# ESP12_Altherma.net
KiCad netlist of a schematic drawn in EAGLE
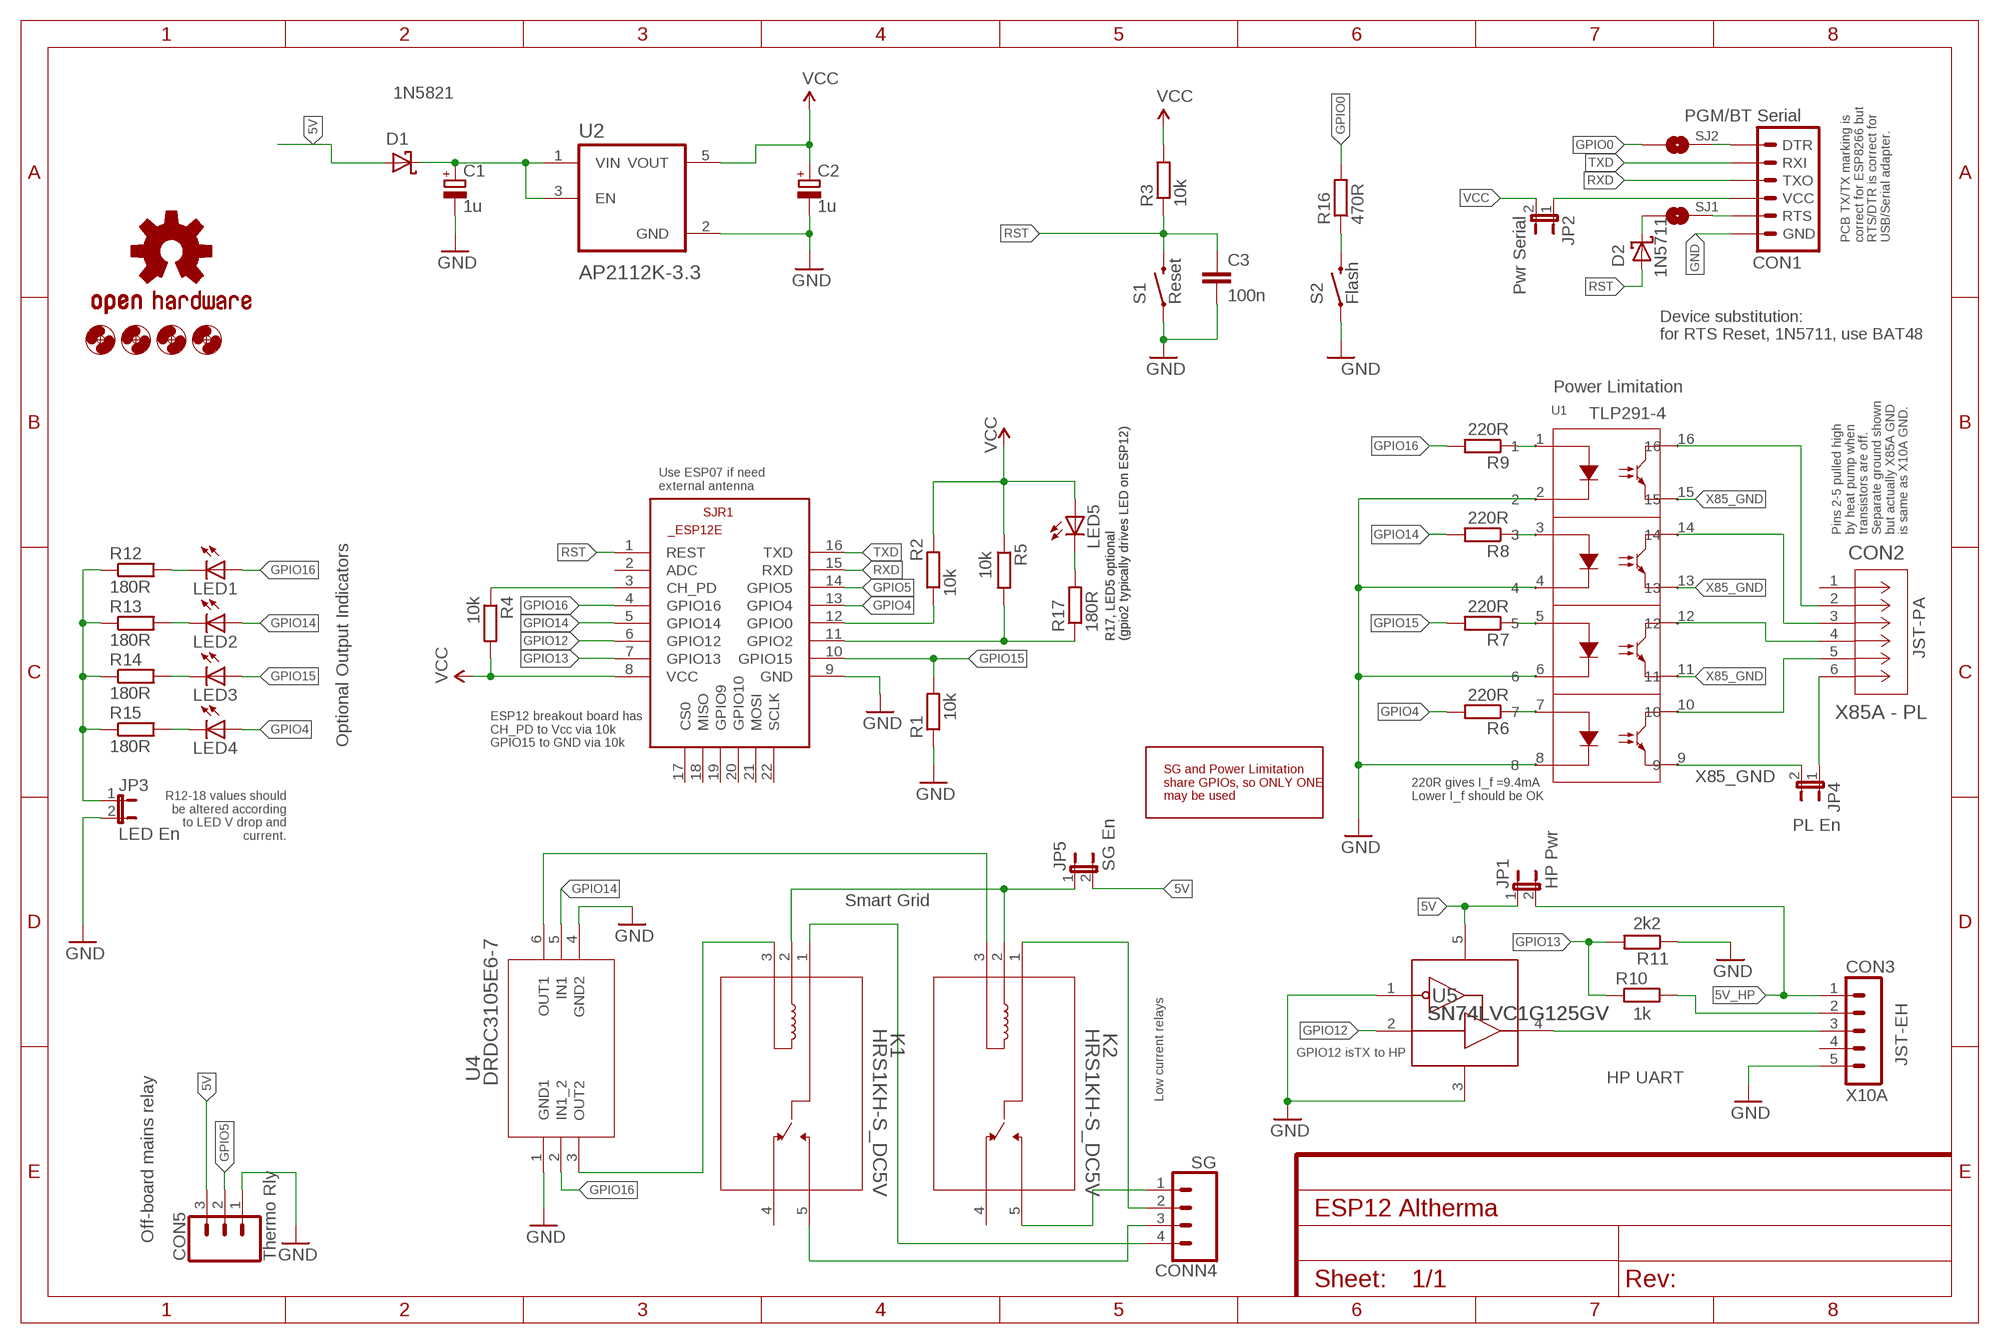
[diagram p0: schematic, sheet 1]

(export (version "E")
  (design (tool "Eeschema 10.0.6"))
  (components
    (comp (ref "C1")
      (value "1u")
      (footprint "eagle-import:E2,5-5")
      (libsource (lib "eagle-import") (part "CPOL-EUE2.5-510UF"))
    )
    (comp (ref "C2")
      (value "1u")
      (footprint "eagle-import:E2,5-5")
      (libsource (lib "eagle-import") (part "CPOL-EUE2.5-510UF"))
    )
    (comp (ref "C3")
      (value "100n")
      (footprint "eagle-import:1206")
      (libsource (lib "eagle-import") (part "C-EU1206"))
    )
    (comp (ref "CON1")
      (value "PGM/BT Serial")
      (footprint "eagle-import:1X06-KIT")
      (libsource (lib "eagle-import") (part "ESP8266_SERIAL_PROGRAM1X06_ESP_SERIAL"))
    )
    (comp (ref "CON2")
      (value "X85A - PL")
      (footprint "eagle-import:CONN_B06B-PASK_JST")
      (fields
        (field (name "MANUFACTURER_PART_NUMBER") "B06B-PASK(LF)(SN)")
        (field (name "COPYRIGHT") "Copyright (C) 2025 Ultra Librarian. All rights reserved.")
      )
      (libsource (lib "eagle-import") (part "B06B-PASK(LF)(SN)"))
    )
    (comp (ref "CON3")
      (value "X10A")
      (footprint "eagle-import:B5B-EH-A")
      (libsource (lib "eagle-import") (part "B5B-EH-A"))
    )
    (comp (ref "CON5")
      (value "Thermo Rly")
      (footprint "eagle-import:1X03")
      (libsource (lib "eagle-import") (part "CONN_03"))
    )
    (comp (ref "CONN4")
      (value "SG")
      (footprint "eagle-import:1X04")
      (libsource (lib "eagle-import") (part "CONN_04PTH"))
    )
    (comp (ref "D1")
      (value "1N5821")
      (footprint "eagle-import:DO201-15")
      (libsource (lib "eagle-import") (part "DIODE-SCHOTTKYDO-201-VERT"))
    )
    (comp (ref "D2")
      (value "1N5711")
      (footprint "eagle-import:DO35-7")
      (libsource (lib "eagle-import") (part "DIODE-SCHOTTKYDO35-7"))
    )
    (comp (ref "H1")
      (value "MOUNT-HOLE3.2")
      (footprint "eagle-import:3,2")
      (libsource (lib "eagle-import") (part "MOUNT-HOLE3.2"))
    )
    (comp (ref "H2")
      (value "MOUNT-HOLE3.2")
      (footprint "eagle-import:3,2")
      (libsource (lib "eagle-import") (part "MOUNT-HOLE3.2"))
    )
    (comp (ref "H3")
      (value "MOUNT-HOLE3.2")
      (footprint "eagle-import:3,2")
      (libsource (lib "eagle-import") (part "MOUNT-HOLE3.2"))
    )
    (comp (ref "H4")
      (value "MOUNT-HOLE3.2")
      (footprint "eagle-import:3,2")
      (libsource (lib "eagle-import") (part "MOUNT-HOLE3.2"))
    )
    (comp (ref "JP1")
      (value "HP Pwr")
      (footprint "eagle-import:1X02")
      (libsource (lib "eagle-import") (part "JUMPER-2PTH"))
    )
    (comp (ref "JP2")
      (value "Pwr Serial")
      (footprint "eagle-import:1X02")
      (libsource (lib "eagle-import") (part "JUMPER-2PTH"))
    )
    (comp (ref "JP3")
      (value "LED En")
      (footprint "eagle-import:1X02")
      (libsource (lib "eagle-import") (part "JUMPER-2PTH"))
    )
    (comp (ref "JP4")
      (value "PL En")
      (footprint "eagle-import:1X02")
      (libsource (lib "eagle-import") (part "JUMPER-2PTH"))
    )
    (comp (ref "JP5")
      (value "SG En")
      (footprint "eagle-import:1X02")
      (libsource (lib "eagle-import") (part "JUMPER-2PTH"))
    )
    (comp (ref "K1")
      (value "HRS1KH-S_DC5V")
      (footprint "eagle-import:HRS1KH-S_DC5V_MTC")
      (fields
        (field (name "MANUFACTURER_PART_NUMBER") "HRS1KH-S DC5V")
        (field (name "COPYRIGHT") "Copyright (C) 2024 Ultra Librarian. All rights reserved.")
      )
      (libsource (lib "eagle-import") (part "HRS1KH-S_DC5V"))
    )
    (comp (ref "K2")
      (value "HRS1KH-S_DC5V")
      (footprint "eagle-import:HRS1KH-S_DC5V_MTC")
      (fields
        (field (name "MANUFACTURER_PART_NUMBER") "HRS1KH-S DC5V")
        (field (name "COPYRIGHT") "Copyright (C) 2024 Ultra Librarian. All rights reserved.")
      )
      (libsource (lib "eagle-import") (part "HRS1KH-S_DC5V"))
    )
    (comp (ref "LED1")
      (value "LED1206")
      (footprint "eagle-import:LED-1206")
      (libsource (lib "eagle-import") (part "LED1206"))
    )
    (comp (ref "LED2")
      (value "LED1206")
      (footprint "eagle-import:LED-1206")
      (libsource (lib "eagle-import") (part "LED1206"))
    )
    (comp (ref "LED3")
      (value "LED1206")
      (footprint "eagle-import:LED-1206")
      (libsource (lib "eagle-import") (part "LED1206"))
    )
    (comp (ref "LED4")
      (value "LED1206")
      (footprint "eagle-import:LED-1206")
      (libsource (lib "eagle-import") (part "LED1206"))
    )
    (comp (ref "LED5")
      (value "LED1206")
      (footprint "eagle-import:LED-1206")
      (libsource (lib "eagle-import") (part "LED1206"))
    )
    (comp (ref "LOGO1")
      (value "OSHW-LOGOM")
      (footprint "eagle-import:OSHW-LOGO-M")
      (libsource (lib "eagle-import") (part "OSHW-LOGOM"))
    )
    (comp (ref "R1")
      (value "10k")
      (footprint "eagle-import:1206")
      (libsource (lib "eagle-import") (part "R-EU_"))
    )
    (comp (ref "R2")
      (value "10k")
      (footprint "eagle-import:1206")
      (libsource (lib "eagle-import") (part "R-EU_"))
    )
    (comp (ref "R3")
      (value "10k")
      (footprint "eagle-import:1206")
      (libsource (lib "eagle-import") (part "R-EU_"))
    )
    (comp (ref "R4")
      (value "10k")
      (footprint "eagle-import:1206")
      (libsource (lib "eagle-import") (part "R-EU_"))
    )
    (comp (ref "R5")
      (value "10k")
      (footprint "eagle-import:1206")
      (libsource (lib "eagle-import") (part "R-EU_"))
    )
    (comp (ref "R6")
      (value "220R")
      (footprint "eagle-import:1206")
      (libsource (lib "eagle-import") (part "R-EU_"))
    )
    (comp (ref "R7")
      (value "220R")
      (footprint "eagle-import:1206")
      (libsource (lib "eagle-import") (part "R-EU_"))
    )
    (comp (ref "R8")
      (value "220R")
      (footprint "eagle-import:1206")
      (libsource (lib "eagle-import") (part "R-EU_"))
    )
    (comp (ref "R9")
      (value "220R")
      (footprint "eagle-import:1206")
      (libsource (lib "eagle-import") (part "R-EU_"))
    )
    (comp (ref "R10")
      (value "1k")
      (footprint "eagle-import:1206")
      (libsource (lib "eagle-import") (part "R-EU_"))
    )
    (comp (ref "R11")
      (value "2k2")
      (footprint "eagle-import:1206")
      (libsource (lib "eagle-import") (part "R-EU_"))
    )
    (comp (ref "R12")
      (value "180R")
      (footprint "eagle-import:1206")
      (libsource (lib "eagle-import") (part "R-EU_"))
    )
    (comp (ref "R13")
      (value "180R")
      (footprint "eagle-import:1206")
      (libsource (lib "eagle-import") (part "R-EU_"))
    )
    (comp (ref "R14")
      (value "180R")
      (footprint "eagle-import:1206")
      (libsource (lib "eagle-import") (part "R-EU_"))
    )
    (comp (ref "R15")
      (value "180R")
      (footprint "eagle-import:1206")
      (libsource (lib "eagle-import") (part "R-EU_"))
    )
    (comp (ref "R16")
      (value "470R")
      (footprint "eagle-import:0204_7")
      (libsource (lib "eagle-import") (part "R-EU_0204/7"))
    )
    (comp (ref "R17")
      (value "180R")
      (footprint "eagle-import:1206")
      (libsource (lib "eagle-import") (part "R-EU_"))
    )
    (comp (ref "S1")
      (value "Reset")
      (footprint "eagle-import:TACTILE-PTH")
      (libsource (lib "eagle-import") (part "SWITCH-MOMENTARY-2PTH"))
    )
    (comp (ref "S2")
      (value "Flash")
      (footprint "eagle-import:TACTILE-PTH")
      (libsource (lib "eagle-import") (part "SWITCH-MOMENTARY-2PTH"))
    )
    (comp (ref "SJ1")
      (value "SOLDERJUMPERTRACE")
      (footprint "eagle-import:SJ_2S-TRACE")
      (libsource (lib "eagle-import") (part "SOLDERJUMPERTRACE"))
    )
    (comp (ref "SJ2")
      (value "SOLDERJUMPERTRACE")
      (footprint "eagle-import:SJ_2S-TRACE")
      (libsource (lib "eagle-import") (part "SOLDERJUMPERTRACE"))
    )
    (comp (ref "SJR1")
      (value "ESP8266-12EESP8266-ESP12E-X")
      (footprint "eagle-import:ESP8266-ESP12E0-NKE")
      (libsource (lib "eagle-import") (part "ESP8266-12EESP8266-ESP12E-X"))
    )
    (comp (ref "U1")
      (value "TLP291-4")
      (footprint "eagle-import:SO16_TOS")
      (fields
        (field (name "MANUFACTURER_PART_NUMBER") "TLP291-4(GB-TP,E)")
        (field (name "COPYRIGHT") "Copyright (C) 2024 Ultra Librarian. All rights reserved.")
      )
      (libsource (lib "eagle-import") (part "TLP291-4(GB-TP,E)"))
    )
    (comp (ref "U2")
      (value "AP2112K-3.3")
      (footprint "eagle-import:SOT95P285X140-5N")
      (fields (field (name "MF") "Diodes Inc.") (field (name "MP") "AP2112K-3.3TRG1"))
      (libsource (lib "eagle-import") (part "AP2112K-3.3TRG1"))
    )
    (comp (ref "U4")
      (value "DRDC3105E6-7")
      (footprint "eagle-import:SOT26-DI_DIO-M")
      (fields (field (name "COPYRIGHT") "Copyright (C) 2024 Ultra Librarian. All rights reserved."))
      (libsource (lib "eagle-import") (part "DRDC3105E6-7SOT26-DI_DIO-M"))
    )
    (comp (ref "U5")
      (value "SN74LVC1G125GV")
      (footprint "eagle-import:DBV0005A_L")
      (fields
        (field (name "MANUFACTURER_PART_NUMBER") "SN74LVC1G125DBVR")
        (field (name "COPYRIGHT") "Copyright (C) 2024 Ultra Librarian. All rights reserved.")
      )
      (libsource (lib "eagle-import") (part "SN74LVC1G125DBVRDBV0005A_L"))
    )
  )
  (nets
    (net (code "1") (name "5V") (class "Default")
      (node (ref "CON5") (pin "3") (pinfunction "3_3") (pintype "passive"))
      (node (ref "D1") (pin "A") (pinfunction "A_A") (pintype "passive"))
      (node (ref "JP1") (pin "1") (pinfunction "1_1") (pintype "passive"))
      (node (ref "JP5") (pin "2") (pinfunction "2_2") (pintype "passive"))
      (node (ref "U5") (pin "5") (pinfunction "VCC_5") (pintype "power_in"))
    )
    (net (code "2") (name "5V_HP") (class "Default")
      (node (ref "CON3") (pin "1") (pinfunction "1_1") (pintype "passive"))
      (node (ref "JP1") (pin "2") (pinfunction "2_2") (pintype "passive"))
    )
    (net (code "3") (name "GND") (class "Default")
      (node (ref "C1") (pin "-") (pinfunction "-_-") (pintype "passive"))
      (node (ref "C2") (pin "-") (pinfunction "-_-") (pintype "passive"))
      (node (ref "C3") (pin "2") (pinfunction "2_2") (pintype "passive"))
      (node (ref "CON1") (pin "1") (pinfunction "GND_1") (pintype "passive"))
      (node (ref "CON3") (pin "5") (pinfunction "5_5") (pintype "passive"))
      (node (ref "CON5") (pin "1") (pinfunction "1_1") (pintype "passive"))
      (node (ref "JP3") (pin "2") (pinfunction "2_2") (pintype "passive"))
      (node (ref "R1") (pin "1") (pinfunction "1_1") (pintype "passive"))
      (node (ref "R11") (pin "1") (pinfunction "1_1") (pintype "passive"))
      (node (ref "S1") (pin "1") (pinfunction "1_1") (pintype "passive"))
      (node (ref "S2") (pin "1") (pinfunction "1_1") (pintype "passive"))
      (node (ref "SJR1") (pin "9") (pinfunction "GND_9") (pintype "bidirectional"))
      (node (ref "U1") (pin "2") (pinfunction "2_2") (pintype "passive"))
      (node (ref "U1") (pin "4") (pinfunction "4_4") (pintype "passive"))
      (node (ref "U1") (pin "6") (pinfunction "6_6") (pintype "passive"))
      (node (ref "U1") (pin "8") (pinfunction "8_8") (pintype "passive"))
      (node (ref "U2") (pin "2") (pinfunction "GND_2") (pintype "power_in"))
      (node (ref "U4") (pin "1") (pinfunction "GND1_1") (pintype "passive"))
      (node (ref "U4") (pin "4") (pinfunction "GND2_4") (pintype "passive"))
      (node (ref "U5") (pin "1") (pinfunction "OE_N_1") (pintype "input"))
      (node (ref "U5") (pin "3") (pinfunction "GND_3") (pintype "power_in"))
    )
    (net (code "4") (name "GPIO0") (class "Default")
      (node (ref "R16") (pin "2") (pinfunction "2_2") (pintype "passive"))
      (node (ref "R2") (pin "1") (pinfunction "1_1") (pintype "passive"))
      (node (ref "SJ2") (pin "1") (pinfunction "1_1") (pintype "passive"))
      (node (ref "SJR1") (pin "12") (pinfunction "GPIO0_12") (pintype "bidirectional"))
    )
    (net (code "5") (name "GPIO4") (class "Default")
      (node (ref "LED4") (pin "A") (pinfunction "A_A") (pintype "passive"))
      (node (ref "R6") (pin "2") (pinfunction "2_2") (pintype "passive"))
      (node (ref "SJR1") (pin "13") (pinfunction "GPIO4_13") (pintype "bidirectional"))
    )
    (net (code "6") (name "GPIO5") (class "Default")
      (node (ref "CON5") (pin "2") (pinfunction "2_2") (pintype "passive"))
      (node (ref "SJR1") (pin "14") (pinfunction "GPIO5_14") (pintype "bidirectional"))
    )
    (net (code "7") (name "GPIO12") (class "Default")
      (node (ref "SJR1") (pin "6") (pinfunction "GPIO12_6") (pintype "bidirectional"))
      (node (ref "U5") (pin "2") (pinfunction "A_2") (pintype "input"))
    )
    (net (code "8") (name "GPIO13") (class "Default")
      (node (ref "R10") (pin "1") (pinfunction "1_1") (pintype "passive"))
      (node (ref "R11") (pin "2") (pinfunction "2_2") (pintype "passive"))
      (node (ref "SJR1") (pin "7") (pinfunction "GPIO13_7") (pintype "bidirectional"))
    )
    (net (code "9") (name "GPIO14") (class "Default")
      (node (ref "LED2") (pin "A") (pinfunction "A_A") (pintype "passive"))
      (node (ref "R8") (pin "2") (pinfunction "2_2") (pintype "passive"))
      (node (ref "SJR1") (pin "5") (pinfunction "GPIO14_5") (pintype "bidirectional"))
      (node (ref "U4") (pin "5") (pinfunction "IN1_5") (pintype "input"))
    )
    (net (code "10") (name "GPIO15") (class "Default")
      (node (ref "LED3") (pin "A") (pinfunction "A_A") (pintype "passive"))
      (node (ref "R1") (pin "2") (pinfunction "2_2") (pintype "passive"))
      (node (ref "R7") (pin "2") (pinfunction "2_2") (pintype "passive"))
      (node (ref "SJR1") (pin "10") (pinfunction "GPIO15_10") (pintype "bidirectional"))
    )
    (net (code "11") (name "GPIO16") (class "Default")
      (node (ref "LED1") (pin "A") (pinfunction "A_A") (pintype "passive"))
      (node (ref "R9") (pin "2") (pinfunction "2_2") (pintype "passive"))
      (node (ref "SJR1") (pin "4") (pinfunction "GPIO16_4") (pintype "bidirectional"))
      (node (ref "U4") (pin "2") (pinfunction "IN1_2_2") (pintype "input"))
    )
    (net (code "12") (name "Net-(CON1-DTR)") (class "Default")
      (node (ref "CON1") (pin "6") (pinfunction "DTR_6") (pintype "passive"))
      (node (ref "SJ2") (pin "2") (pinfunction "2_2") (pintype "passive"))
    )
    (net (code "13") (name "Net-(CON1-RTS)") (class "Default")
      (node (ref "CON1") (pin "2") (pinfunction "RTS_2") (pintype "passive"))
      (node (ref "SJ1") (pin "2") (pinfunction "2_2") (pintype "passive"))
    )
    (net (code "14") (name "Net-(CON1-VCC)") (class "Default")
      (node (ref "CON1") (pin "3") (pinfunction "VCC_3") (pintype "passive"))
      (node (ref "JP2") (pin "1") (pinfunction "1_1") (pintype "passive"))
    )
    (net (code "15") (name "Net-(CON2-Pad2)") (class "Default")
      (node (ref "CON2") (pin "2") (pinfunction "2_2") (pintype "passive"))
      (node (ref "U1") (pin "16") (pinfunction "16_16") (pintype "passive"))
    )
    (net (code "16") (name "Net-(CON2-Pad3)") (class "Default")
      (node (ref "CON2") (pin "3") (pinfunction "3_3") (pintype "passive"))
      (node (ref "U1") (pin "14") (pinfunction "14_14") (pintype "passive"))
    )
    (net (code "17") (name "Net-(CON2-Pad4)") (class "Default")
      (node (ref "CON2") (pin "4") (pinfunction "4_4") (pintype "passive"))
      (node (ref "U1") (pin "12") (pinfunction "12_12") (pintype "passive"))
    )
    (net (code "18") (name "Net-(CON2-Pad5)") (class "Default")
      (node (ref "CON2") (pin "5") (pinfunction "5_5") (pintype "passive"))
      (node (ref "U1") (pin "10") (pinfunction "10_10") (pintype "passive"))
    )
    (net (code "19") (name "Net-(CON2-Pad6)") (class "Default")
      (node (ref "CON2") (pin "6") (pinfunction "6_6") (pintype "passive"))
      (node (ref "JP4") (pin "1") (pinfunction "1_1") (pintype "passive"))
    )
    (net (code "20") (name "Net-(CON3-Pad2)") (class "Default")
      (node (ref "CON3") (pin "2") (pinfunction "2_2") (pintype "passive"))
      (node (ref "R10") (pin "2") (pinfunction "2_2") (pintype "passive"))
    )
    (net (code "21") (name "Net-(CONN4-Pad1)") (class "Default")
      (node (ref "CONN4") (pin "1") (pinfunction "1_1") (pintype "passive"))
      (node (ref "K2") (pin "5") (pinfunction "5_5") (pintype "passive"))
    )
    (net (code "22") (name "Net-(CONN4-Pad2)") (class "Default")
      (node (ref "CONN4") (pin "2") (pinfunction "2_2") (pintype "passive"))
      (node (ref "K2") (pin "1") (pinfunction "1_1") (pintype "passive"))
    )
    (net (code "23") (name "Net-(CONN4-Pad3)") (class "Default")
      (node (ref "CONN4") (pin "3") (pinfunction "3_3") (pintype "passive"))
      (node (ref "K1") (pin "5") (pinfunction "5_5") (pintype "passive"))
    )
    (net (code "24") (name "Net-(CONN4-Pad4)") (class "Default")
      (node (ref "CONN4") (pin "4") (pinfunction "4_4") (pintype "passive"))
      (node (ref "K1") (pin "1") (pinfunction "1_1") (pintype "passive"))
    )
    (net (code "25") (name "Net-(D2-PadC)") (class "Default")
      (node (ref "D2") (pin "C") (pinfunction "C_C") (pintype "passive"))
      (node (ref "SJ1") (pin "1") (pinfunction "1_1") (pintype "passive"))
    )
    (net (code "26") (name "Net-(JP3-Pad1)") (class "Default")
      (node (ref "JP3") (pin "1") (pinfunction "1_1") (pintype "passive"))
      (node (ref "R12") (pin "1") (pinfunction "1_1") (pintype "passive"))
      (node (ref "R13") (pin "1") (pinfunction "1_1") (pintype "passive"))
      (node (ref "R14") (pin "1") (pinfunction "1_1") (pintype "passive"))
      (node (ref "R15") (pin "1") (pinfunction "1_1") (pintype "passive"))
    )
    (net (code "27") (name "Net-(JP5-Pad1)") (class "Default")
      (node (ref "JP5") (pin "1") (pinfunction "1_1") (pintype "passive"))
      (node (ref "K1") (pin "2") (pinfunction "2_2") (pintype "passive"))
      (node (ref "K2") (pin "2") (pinfunction "2_2") (pintype "passive"))
    )
    (net (code "28") (name "Net-(LED1-PadC)") (class "Default")
      (node (ref "LED1") (pin "C") (pinfunction "C_C") (pintype "passive"))
      (node (ref "R12") (pin "2") (pinfunction "2_2") (pintype "passive"))
    )
    (net (code "29") (name "Net-(LED2-PadC)") (class "Default")
      (node (ref "LED2") (pin "C") (pinfunction "C_C") (pintype "passive"))
      (node (ref "R13") (pin "2") (pinfunction "2_2") (pintype "passive"))
    )
    (net (code "30") (name "Net-(LED3-PadC)") (class "Default")
      (node (ref "LED3") (pin "C") (pinfunction "C_C") (pintype "passive"))
      (node (ref "R14") (pin "2") (pinfunction "2_2") (pintype "passive"))
    )
    (net (code "31") (name "Net-(LED4-PadC)") (class "Default")
      (node (ref "LED4") (pin "C") (pinfunction "C_C") (pintype "passive"))
      (node (ref "R15") (pin "2") (pinfunction "2_2") (pintype "passive"))
    )
    (net (code "32") (name "Net-(LED5-PadC)") (class "Default")
      (node (ref "LED5") (pin "C") (pinfunction "C_C") (pintype "passive"))
      (node (ref "R17") (pin "2") (pinfunction "2_2") (pintype "passive"))
    )
    (net (code "33") (name "Net-(R6-Pad1)") (class "Default")
      (node (ref "R6") (pin "1") (pinfunction "1_1") (pintype "passive"))
      (node (ref "U1") (pin "7") (pinfunction "7_7") (pintype "passive"))
    )
    (net (code "34") (name "Net-(R7-Pad1)") (class "Default")
      (node (ref "R7") (pin "1") (pinfunction "1_1") (pintype "passive"))
      (node (ref "U1") (pin "5") (pinfunction "5_5") (pintype "passive"))
    )
    (net (code "35") (name "Net-(R8-Pad1)") (class "Default")
      (node (ref "R8") (pin "1") (pinfunction "1_1") (pintype "passive"))
      (node (ref "U1") (pin "3") (pinfunction "3_3") (pintype "passive"))
    )
    (net (code "36") (name "Net-(R9-Pad1)") (class "Default")
      (node (ref "R9") (pin "1") (pinfunction "1_1") (pintype "passive"))
      (node (ref "U1") (pin "1") (pinfunction "1_1") (pintype "passive"))
    )
    (net (code "37") (name "Net-(S2-2)") (class "Default")
      (node (ref "R16") (pin "1") (pinfunction "1_1") (pintype "passive"))
      (node (ref "S2") (pin "3") (pinfunction "2_3") (pintype "passive"))
    )
    (net (code "38") (name "Net-(SJR1-CH_PD)") (class "Default")
      (node (ref "R4") (pin "1") (pinfunction "1_1") (pintype "passive"))
      (node (ref "SJR1") (pin "3") (pinfunction "CH_PD_3") (pintype "bidirectional"))
    )
    (net (code "39") (name "Net-(SJR1-GPIO2)") (class "Default")
      (node (ref "R17") (pin "1") (pinfunction "1_1") (pintype "passive"))
      (node (ref "R5") (pin "2") (pinfunction "2_2") (pintype "passive"))
      (node (ref "SJR1") (pin "11") (pinfunction "GPIO2_11") (pintype "bidirectional"))
    )
    (net (code "40") (name "Net-(U2-EN)") (class "Default")
      (node (ref "C1") (pin "+") (pinfunction "+_+") (pintype "passive"))
      (node (ref "D1") (pin "C") (pinfunction "C_C") (pintype "passive"))
      (node (ref "U2") (pin "1") (pinfunction "VIN_1") (pintype "power_in"))
      (node (ref "U2") (pin "3") (pinfunction "EN_3") (pintype "input"))
    )
    (net (code "41") (name "Net-(U4-OUT1)") (class "Default")
      (node (ref "K2") (pin "3") (pinfunction "3_3") (pintype "passive"))
      (node (ref "U4") (pin "6") (pinfunction "OUT1_6") (pintype "output"))
    )
    (net (code "42") (name "Net-(U4-OUT2)") (class "Default")
      (node (ref "K1") (pin "3") (pinfunction "3_3") (pintype "passive"))
      (node (ref "U4") (pin "3") (pinfunction "OUT2_3") (pintype "output"))
    )
    (net (code "43") (name "Net-(U5-Y)") (class "Default")
      (node (ref "CON3") (pin "3") (pinfunction "3_3") (pintype "passive"))
      (node (ref "U5") (pin "4") (pinfunction "Y_4") (pintype "tri_state"))
    )
    (net (code "44") (name "RST") (class "Default")
      (node (ref "C3") (pin "1") (pinfunction "1_1") (pintype "passive"))
      (node (ref "D2") (pin "A") (pinfunction "A_A") (pintype "passive"))
      (node (ref "R3") (pin "1") (pinfunction "1_1") (pintype "passive"))
      (node (ref "S1") (pin "3") (pinfunction "2_3") (pintype "passive"))
      (node (ref "SJR1") (pin "1") (pinfunction "REST_1") (pintype "bidirectional"))
    )
    (net (code "45") (name "RXD") (class "Default")
      (node (ref "CON1") (pin "4") (pinfunction "TXO_4") (pintype "passive"))
      (node (ref "SJR1") (pin "15") (pinfunction "RXD_15") (pintype "bidirectional"))
    )
    (net (code "46") (name "TXD") (class "Default")
      (node (ref "CON1") (pin "5") (pinfunction "RXI_5") (pintype "passive"))
      (node (ref "SJR1") (pin "16") (pinfunction "TXD_16") (pintype "bidirectional"))
    )
    (net (code "47") (name "VCC") (class "Default")
      (node (ref "C2") (pin "+") (pinfunction "+_+") (pintype "passive"))
      (node (ref "JP2") (pin "2") (pinfunction "2_2") (pintype "passive"))
      (node (ref "LED5") (pin "A") (pinfunction "A_A") (pintype "passive"))
      (node (ref "R2") (pin "2") (pinfunction "2_2") (pintype "passive"))
      (node (ref "R3") (pin "2") (pinfunction "2_2") (pintype "passive"))
      (node (ref "R4") (pin "2") (pinfunction "2_2") (pintype "passive"))
      (node (ref "R5") (pin "1") (pinfunction "1_1") (pintype "passive"))
      (node (ref "SJR1") (pin "8") (pinfunction "VCC_8") (pintype "bidirectional"))
      (node (ref "U2") (pin "5") (pinfunction "VOUT_5") (pintype "power_in"))
    )
    (net (code "48") (name "X85_GND") (class "Default")
      (node (ref "JP4") (pin "2") (pinfunction "2_2") (pintype "passive"))
      (node (ref "U1") (pin "11") (pinfunction "11_11") (pintype "passive"))
      (node (ref "U1") (pin "13") (pinfunction "13_13") (pintype "passive"))
      (node (ref "U1") (pin "15") (pinfunction "15_15") (pintype "passive"))
      (node (ref "U1") (pin "9") (pinfunction "9_9") (pintype "passive"))
    )
    (net (code "49") (name "unconnected-(CON2-Pad1)") (class "Default")
      (node (ref "CON2") (pin "1") (pinfunction "1_1") (pintype "passive"))
    )
    (net (code "50") (name "unconnected-(CON3-Pad4)") (class "Default")
      (node (ref "CON3") (pin "4") (pinfunction "4_4") (pintype "passive"))
    )
    (net (code "51") (name "unconnected-(K1-Pad4)") (class "Default")
      (node (ref "K1") (pin "4") (pinfunction "4_4") (pintype "passive"))
    )
    (net (code "52") (name "unconnected-(K2-Pad4)") (class "Default")
      (node (ref "K2") (pin "4") (pinfunction "4_4") (pintype "passive"))
    )
    (net (code "53") (name "unconnected-(SJR1-ADC-Pad2)") (class "Default")
      (node (ref "SJR1") (pin "2") (pinfunction "ADC_2") (pintype "bidirectional"))
    )
    (net (code "54") (name "unconnected-(SJR1-CS0-Pad17)") (class "Default")
      (node (ref "SJR1") (pin "17") (pinfunction "CS0_17") (pintype "bidirectional"))
    )
    (net (code "55") (name "unconnected-(SJR1-GPIO9-Pad19)") (class "Default")
      (node (ref "SJR1") (pin "19") (pinfunction "GPIO9_19") (pintype "bidirectional"))
    )
    (net (code "56") (name "unconnected-(SJR1-GPIO10-Pad20)") (class "Default")
      (node (ref "SJR1") (pin "20") (pinfunction "GPIO10_20") (pintype "bidirectional"))
    )
    (net (code "57") (name "unconnected-(SJR1-MISO-Pad18)") (class "Default")
      (node (ref "SJR1") (pin "18") (pinfunction "MISO_18") (pintype "bidirectional"))
    )
    (net (code "58") (name "unconnected-(SJR1-MOSI-Pad21)") (class "Default")
      (node (ref "SJR1") (pin "21") (pinfunction "MOSI_21") (pintype "bidirectional"))
    )
    (net (code "59") (name "unconnected-(SJR1-SCLK-Pad22)") (class "Default")
      (node (ref "SJR1") (pin "22") (pinfunction "SCLK_22") (pintype "bidirectional"))
    )
  )
)
